# MC_Sch_1.net
KiCad netlist of a schematic drawn in Altium Designer
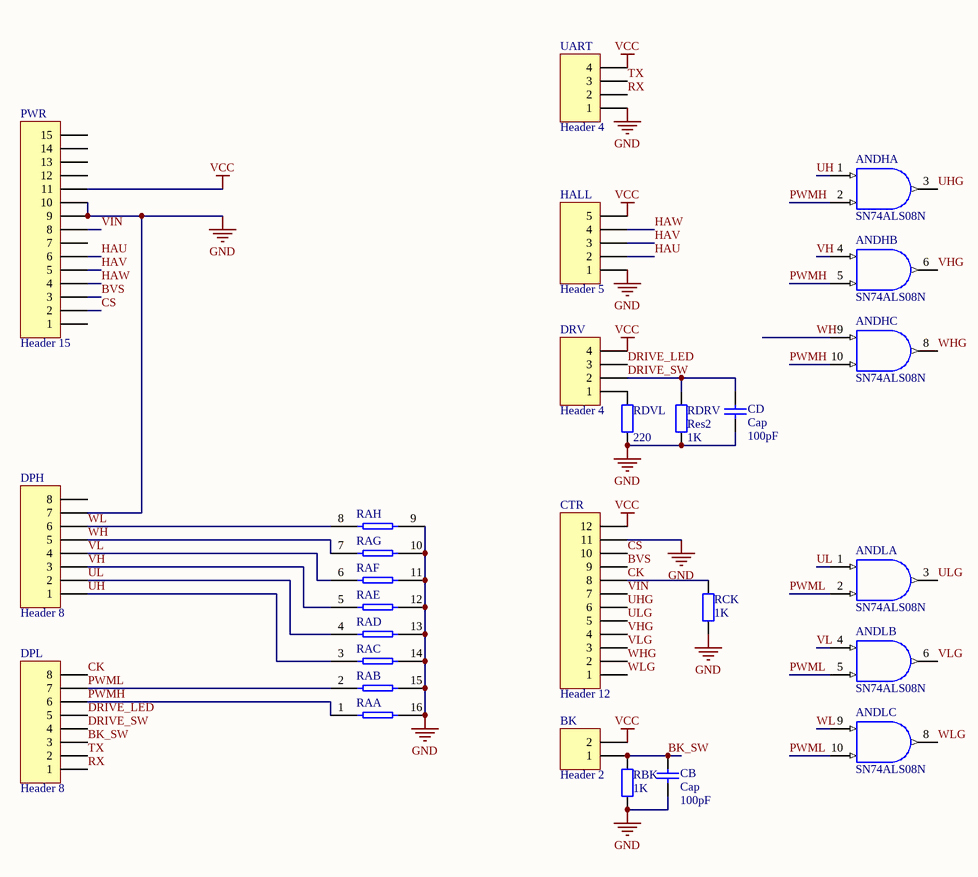
[diagram p0: MC_Sch_1.SchDoc]

(export (version "E")
  (design (tool "Eeschema 10.0.6"))
  (components
    (comp (ref "ANDH")
      (value "SN74ALS08N")
      (footprint "N014")
      (description "Quadruple 2-Input Positive-AND Gate")
      (fields (field (name "PUBLISHER") "Altium Limited"))
      (libsource (lib "TI Logic Gate 1") (part "SN74ALS08N"))
    )
    (comp (ref "ANDL")
      (value "SN74ALS08N")
      (footprint "N014")
      (description "Quadruple 2-Input Positive-AND Gate")
      (fields (field (name "PUBLISHER") "Altium Limited"))
      (libsource (lib "TI Logic Gate 1") (part "SN74ALS08N"))
    )
    (comp (ref "BK")
      (value "Header 2")
      (footprint "HDR1X2")
      (description "Header, 2-Pin")
      (fields (field (name "PUBLISHER") "Altium Limited"))
      (libsource (lib "Miscellaneous Connectors") (part "Header 2"))
    )
    (comp (ref "CB")
      (value "Cap")
      (footprint "CBB 6.3*6.3*5")
      (description "Capacitor")
      (fields (field (name "ALTIUM_VALUE") "100pF") (field (name "PUBLISHER") "Altium Limited"))
      (libsource (lib "Miscellaneous Devices") (part "Cap"))
    )
    (comp (ref "CD")
      (value "Cap")
      (footprint "CBB 6.3*6.3*5")
      (description "Capacitor")
      (fields (field (name "ALTIUM_VALUE") "100pF") (field (name "PUBLISHER") "Altium Limited"))
      (libsource (lib "Miscellaneous Devices") (part "Cap"))
    )
    (comp (ref "CTR")
      (value "Header 12")
      (footprint "HDR1X12")
      (description "Header, 12-Pin")
      (fields (field (name "PUBLISHER") "Altium Limited"))
      (libsource (lib "Miscellaneous Connectors") (part "Header 12"))
    )
    (comp (ref "DPH")
      (value "Header 8")
      (footprint "HDR1X8")
      (description "Header, 8-Pin")
      (fields (field (name "PUBLISHER") "Altium Limited"))
      (libsource (lib "Miscellaneous Connectors") (part "Header 8"))
    )
    (comp (ref "DPL")
      (value "Header 8")
      (footprint "HDR1X8")
      (description "Header, 8-Pin")
      (fields (field (name "PUBLISHER") "Altium Limited"))
      (libsource (lib "Miscellaneous Connectors") (part "Header 8"))
    )
    (comp (ref "DRV")
      (value "Header 4")
      (footprint "HDR1X4")
      (description "Header, 4-Pin")
      (fields (field (name "PUBLISHER") "Altium Limited"))
      (libsource (lib "Miscellaneous Connectors") (part "Header 4"))
    )
    (comp (ref "HALL")
      (value "Header 5")
      (footprint "HDR1X5")
      (description "Header, 5-Pin")
      (fields (field (name "PUBLISHER") "Altium Limited"))
      (libsource (lib "Miscellaneous Connectors") (part "Header 5"))
    )
    (comp (ref "PWR")
      (value "Header 15")
      (footprint "HDR1X15")
      (description "Header, 15-Pin")
      (fields (field (name "PUBLISHER") "Altium Limited"))
      (libsource (lib "Miscellaneous Connectors") (part "Header 15"))
    )
    (comp (ref "RA")
      (value "Res Pack2")
      (footprint "DIP-16")
      (description "Isolated Resistor Network - Parts")
      (fields (field (name "PUBLISHER") "Altium Limited"))
      (libsource (lib "Miscellaneous Devices") (part "Res Pack2"))
    )
    (comp (ref "RBK")
      (value "1K")
      (footprint "AXIAL-0.4")
      (description "Resistor")
      (fields (field (name "Comment") "Res2") (field (name "PUBLISHER") "Altium Limited"))
      (libsource (lib "Miscellaneous Devices") (part "Res2"))
    )
    (comp (ref "RCK")
      (value "1K")
      (footprint "AXIAL-0.4")
      (description "Resistor")
      (fields (field (name "Comment") "Res2") (field (name "PUBLISHER") "Altium Limited"))
      (libsource (lib "Miscellaneous Devices") (part "Res2"))
    )
    (comp (ref "RDRV")
      (value "Res2")
      (footprint "AXIAL-0.4")
      (description "Resistor")
      (fields (field (name "ALTIUM_VALUE") "1K") (field (name "PUBLISHER") "Altium Limited"))
      (libsource (lib "Miscellaneous Devices") (part "Res2"))
    )
    (comp (ref "RDVL")
      (value "220")
      (footprint "AXIAL-0.4")
      (description "Resistor")
      (fields (field (name "Comment") "Res2") (field (name "PUBLISHER") "Altium Limited"))
      (libsource (lib "Miscellaneous Devices") (part "Res2"))
    )
    (comp (ref "UART")
      (value "Header 4")
      (footprint "HDR1X4")
      (description "Header, 4-Pin")
      (fields (field (name "PUBLISHER") "Altium Limited"))
      (libsource (lib "Miscellaneous Connectors") (part "Header 4"))
    )
  )
  (nets
    (net (code "1") (name "/BK_SW") (class "Default")
      (node (ref "BK") (pin "1") (pinfunction "1_1") (pintype "passive"))
      (node (ref "CB") (pin "2") (pinfunction "2_2") (pintype "passive"))
      (node (ref "DPL") (pin "3") (pinfunction "3_3") (pintype "passive"))
      (node (ref "RBK") (pin "2") (pinfunction "2_2") (pintype "passive"))
    )
    (net (code "2") (name "/BVS") (class "Default")
      (node (ref "CTR") (pin "9") (pinfunction "9_9") (pintype "passive"))
      (node (ref "PWR") (pin "3") (pinfunction "3_3") (pintype "passive"))
    )
    (net (code "3") (name "/CK") (class "Default")
      (node (ref "CTR") (pin "8") (pinfunction "8_8") (pintype "passive"))
      (node (ref "DPL") (pin "8") (pinfunction "8_8") (pintype "passive"))
      (node (ref "RCK") (pin "2") (pinfunction "2_2") (pintype "passive"))
    )
    (net (code "4") (name "/CS") (class "Default")
      (node (ref "CTR") (pin "10") (pinfunction "10_10") (pintype "passive"))
      (node (ref "PWR") (pin "2") (pinfunction "2_2") (pintype "passive"))
    )
    (net (code "5") (name "/DRIVE_LED") (class "Default")
      (node (ref "DPL") (pin "5") (pinfunction "5_5") (pintype "passive"))
      (node (ref "DRV") (pin "3") (pinfunction "3_3") (pintype "passive"))
    )
    (net (code "6") (name "/DRIVE_SW") (class "Default")
      (node (ref "CD") (pin "2") (pinfunction "2_2") (pintype "passive"))
      (node (ref "DPL") (pin "4") (pinfunction "4_4") (pintype "passive"))
      (node (ref "DRV") (pin "2") (pinfunction "2_2") (pintype "passive"))
      (node (ref "RDRV") (pin "2") (pinfunction "2_2") (pintype "passive"))
    )
    (net (code "7") (name "/HAU") (class "Default")
      (node (ref "HALL") (pin "2") (pinfunction "2_2") (pintype "passive"))
      (node (ref "PWR") (pin "6") (pinfunction "6_6") (pintype "passive"))
    )
    (net (code "8") (name "/HAV") (class "Default")
      (node (ref "HALL") (pin "3") (pinfunction "3_3") (pintype "passive"))
      (node (ref "PWR") (pin "5") (pinfunction "5_5") (pintype "passive"))
    )
    (net (code "9") (name "/HAW") (class "Default")
      (node (ref "HALL") (pin "4") (pinfunction "4_4") (pintype "passive"))
      (node (ref "PWR") (pin "4") (pinfunction "4_4") (pintype "passive"))
    )
    (net (code "10") (name "/PWMH") (class "Default")
      (node (ref "ANDH") (pin "10") (pinfunction "B_10") (pintype "input"))
      (node (ref "ANDH") (pin "2") (pinfunction "B_2") (pintype "input"))
      (node (ref "ANDH") (pin "5") (pinfunction "B_5") (pintype "input"))
      (node (ref "DPL") (pin "6") (pinfunction "6_6") (pintype "passive"))
      (node (ref "RA") (pin "1") (pinfunction "1_1") (pintype "passive"))
    )
    (net (code "11") (name "/PWML") (class "Default")
      (node (ref "ANDL") (pin "10") (pinfunction "B_10") (pintype "input"))
      (node (ref "ANDL") (pin "2") (pinfunction "B_2") (pintype "input"))
      (node (ref "ANDL") (pin "5") (pinfunction "B_5") (pintype "input"))
      (node (ref "DPL") (pin "7") (pinfunction "7_7") (pintype "passive"))
      (node (ref "RA") (pin "2") (pinfunction "2_2") (pintype "passive"))
    )
    (net (code "12") (name "/RX") (class "Default")
      (node (ref "DPL") (pin "1") (pinfunction "1_1") (pintype "passive"))
      (node (ref "UART") (pin "2") (pinfunction "2_2") (pintype "passive"))
    )
    (net (code "13") (name "/TX") (class "Default")
      (node (ref "DPL") (pin "2") (pinfunction "2_2") (pintype "passive"))
      (node (ref "UART") (pin "3") (pinfunction "3_3") (pintype "passive"))
    )
    (net (code "14") (name "/UH") (class "Default")
      (node (ref "ANDH") (pin "1") (pinfunction "A_1") (pintype "input"))
      (node (ref "DPH") (pin "1") (pinfunction "1_1") (pintype "passive"))
      (node (ref "RA") (pin "3") (pinfunction "3_3") (pintype "passive"))
    )
    (net (code "15") (name "/UHG") (class "Default")
      (node (ref "ANDH") (pin "3") (pinfunction "Y_3") (pintype "output"))
      (node (ref "CTR") (pin "6") (pinfunction "6_6") (pintype "passive"))
    )
    (net (code "16") (name "/UL") (class "Default")
      (node (ref "ANDL") (pin "1") (pinfunction "A_1") (pintype "input"))
      (node (ref "DPH") (pin "2") (pinfunction "2_2") (pintype "passive"))
      (node (ref "RA") (pin "4") (pinfunction "4_4") (pintype "passive"))
    )
    (net (code "17") (name "/ULG") (class "Default")
      (node (ref "ANDL") (pin "3") (pinfunction "Y_3") (pintype "output"))
      (node (ref "CTR") (pin "5") (pinfunction "5_5") (pintype "passive"))
    )
    (net (code "18") (name "/VH") (class "Default")
      (node (ref "ANDH") (pin "4") (pinfunction "A_4") (pintype "input"))
      (node (ref "DPH") (pin "3") (pinfunction "3_3") (pintype "passive"))
      (node (ref "RA") (pin "5") (pinfunction "5_5") (pintype "passive"))
    )
    (net (code "19") (name "/VHG") (class "Default")
      (node (ref "ANDH") (pin "6") (pinfunction "Y_6") (pintype "output"))
      (node (ref "CTR") (pin "4") (pinfunction "4_4") (pintype "passive"))
    )
    (net (code "20") (name "/VIN") (class "Default")
      (node (ref "CTR") (pin "7") (pinfunction "7_7") (pintype "passive"))
      (node (ref "PWR") (pin "8") (pinfunction "8_8") (pintype "passive"))
    )
    (net (code "21") (name "/VL") (class "Default")
      (node (ref "ANDL") (pin "4") (pinfunction "A_4") (pintype "input"))
      (node (ref "DPH") (pin "4") (pinfunction "4_4") (pintype "passive"))
      (node (ref "RA") (pin "6") (pinfunction "6_6") (pintype "passive"))
    )
    (net (code "22") (name "/VLG") (class "Default")
      (node (ref "ANDL") (pin "6") (pinfunction "Y_6") (pintype "output"))
      (node (ref "CTR") (pin "3") (pinfunction "3_3") (pintype "passive"))
    )
    (net (code "23") (name "/WH") (class "Default")
      (node (ref "ANDH") (pin "9") (pinfunction "A_9") (pintype "input"))
      (node (ref "DPH") (pin "5") (pinfunction "5_5") (pintype "passive"))
      (node (ref "RA") (pin "7") (pinfunction "7_7") (pintype "passive"))
    )
    (net (code "24") (name "/WHG") (class "Default")
      (node (ref "ANDH") (pin "8") (pinfunction "Y_8") (pintype "output"))
      (node (ref "CTR") (pin "2") (pinfunction "2_2") (pintype "passive"))
    )
    (net (code "25") (name "/WL") (class "Default")
      (node (ref "ANDL") (pin "9") (pinfunction "A_9") (pintype "input"))
      (node (ref "DPH") (pin "6") (pinfunction "6_6") (pintype "passive"))
      (node (ref "RA") (pin "8") (pinfunction "8_8") (pintype "passive"))
    )
    (net (code "26") (name "/WLG") (class "Default")
      (node (ref "ANDL") (pin "8") (pinfunction "Y_8") (pintype "output"))
      (node (ref "CTR") (pin "1") (pinfunction "1_1") (pintype "passive"))
    )
    (net (code "27") (name "GND") (class "Default")
      (node (ref "ANDH") (pin "7") (pinfunction "GND_7") (pintype "power_in"))
      (node (ref "ANDL") (pin "7") (pinfunction "GND_7") (pintype "power_in"))
      (node (ref "CB") (pin "1") (pinfunction "1_1") (pintype "passive"))
      (node (ref "CD") (pin "1") (pinfunction "1_1") (pintype "passive"))
      (node (ref "CTR") (pin "11") (pinfunction "11_11") (pintype "passive"))
      (node (ref "DPH") (pin "7") (pinfunction "7_7") (pintype "passive"))
      (node (ref "HALL") (pin "1") (pinfunction "1_1") (pintype "passive"))
      (node (ref "PWR") (pin "10") (pinfunction "10_10") (pintype "passive"))
      (node (ref "PWR") (pin "9") (pinfunction "9_9") (pintype "passive"))
      (node (ref "RA") (pin "10") (pinfunction "10_10") (pintype "passive"))
      (node (ref "RA") (pin "11") (pinfunction "11_11") (pintype "passive"))
      (node (ref "RA") (pin "12") (pinfunction "12_12") (pintype "passive"))
      (node (ref "RA") (pin "13") (pinfunction "13_13") (pintype "passive"))
      (node (ref "RA") (pin "14") (pinfunction "14_14") (pintype "passive"))
      (node (ref "RA") (pin "15") (pinfunction "15_15") (pintype "passive"))
      (node (ref "RA") (pin "16") (pinfunction "16_16") (pintype "passive"))
      (node (ref "RA") (pin "9") (pinfunction "9_9") (pintype "passive"))
      (node (ref "RBK") (pin "1") (pinfunction "1_1") (pintype "passive"))
      (node (ref "RCK") (pin "1") (pinfunction "1_1") (pintype "passive"))
      (node (ref "RDRV") (pin "1") (pinfunction "1_1") (pintype "passive"))
      (node (ref "RDVL") (pin "1") (pinfunction "1_1") (pintype "passive"))
      (node (ref "UART") (pin "1") (pinfunction "1_1") (pintype "passive"))
    )
    (net (code "28") (name "Net-(DRV-Pad1)") (class "Default")
      (node (ref "DRV") (pin "1") (pinfunction "1_1") (pintype "passive"))
      (node (ref "RDVL") (pin "2") (pinfunction "2_2") (pintype "passive"))
    )
    (net (code "29") (name "VCC") (class "Default")
      (node (ref "ANDH") (pin "14") (pinfunction "VCC_14") (pintype "power_in"))
      (node (ref "ANDL") (pin "14") (pinfunction "VCC_14") (pintype "power_in"))
      (node (ref "BK") (pin "2") (pinfunction "2_2") (pintype "passive"))
      (node (ref "CTR") (pin "12") (pinfunction "12_12") (pintype "passive"))
      (node (ref "DRV") (pin "4") (pinfunction "4_4") (pintype "passive"))
      (node (ref "HALL") (pin "5") (pinfunction "5_5") (pintype "passive"))
      (node (ref "PWR") (pin "11") (pinfunction "11_11") (pintype "passive"))
      (node (ref "UART") (pin "4") (pinfunction "4_4") (pintype "passive"))
    )
    (net (code "30") (name "unconnected-(DPH-Pad8)") (class "Default")
      (node (ref "DPH") (pin "8") (pinfunction "8_8") (pintype "passive"))
    )
    (net (code "31") (name "unconnected-(PWR-Pad1)") (class "Default")
      (node (ref "PWR") (pin "1") (pinfunction "1_1") (pintype "passive"))
    )
    (net (code "32") (name "unconnected-(PWR-Pad7)") (class "Default")
      (node (ref "PWR") (pin "7") (pinfunction "7_7") (pintype "passive"))
    )
    (net (code "33") (name "unconnected-(PWR-Pad12)") (class "Default")
      (node (ref "PWR") (pin "12") (pinfunction "12_12") (pintype "passive"))
    )
    (net (code "34") (name "unconnected-(PWR-Pad13)") (class "Default")
      (node (ref "PWR") (pin "13") (pinfunction "13_13") (pintype "passive"))
    )
    (net (code "35") (name "unconnected-(PWR-Pad14)") (class "Default")
      (node (ref "PWR") (pin "14") (pinfunction "14_14") (pintype "passive"))
    )
    (net (code "36") (name "unconnected-(PWR-Pad15)") (class "Default")
      (node (ref "PWR") (pin "15") (pinfunction "15_15") (pintype "passive"))
    )
  )
)
